# PCB_ESP_BUCK_PS.net
KiCad netlist of a schematic drawn in EAGLE
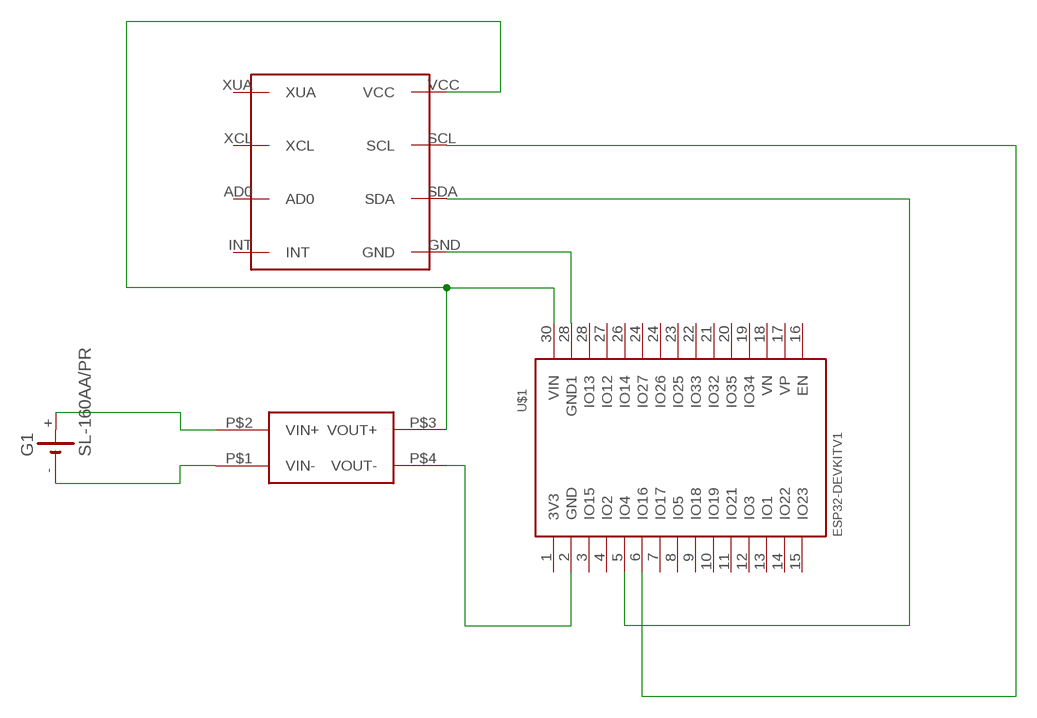
[diagram p0: schematic, sheet 1]

(export (version "E")
  (design (tool "Eeschema 10.0.6"))
  (components
    (comp (ref "G1")
      (value "SL-160AA/PR")
      (footprint "eagle-import:SL-160AA_PR")
      (libsource (lib "eagle-import") (part "SL-160AA/PR"))
    )
    (comp (ref "U$1")
      (value "ESP32DEVKITV1")
      (footprint "eagle-import:ESP32-DEVKITV1")
      (libsource (lib "eagle-import") (part "ESP32DEVKITV1"))
    )
    (comp (ref "U$2")
      (value "MP1584-MINI")
      (footprint "eagle-import:MINI-DC-BRICK")
      (libsource (lib "eagle-import") (part "MP1584-MINI"))
    )
    (comp (ref "U$3")
      (value "MPU-6050")
      (footprint "eagle-import:MPU-6050")
      (libsource (lib "eagle-import") (part "MPU-6050"))
    )
  )
  (nets
    (net (code "1") (name "Net-(U$1-GND)") (class "Default")
      (node (ref "U$1") (pin "2") (pinfunction "GND_2") (pintype "bidirectional"))
      (node (ref "U$2") (pin "P$4") (pinfunction "VOUT-_P$4") (pintype "output"))
    )
    (net (code "2") (name "Net-(U$1-GND1)") (class "Default")
      (node (ref "U$1") (pin "28") (pinfunction "GND1_28") (pintype "bidirectional"))
      (node (ref "U$3") (pin "GND") (pinfunction "GND_GND") (pintype "bidirectional"))
    )
    (net (code "3") (name "Net-(U$1-IO4)") (class "Default")
      (node (ref "U$1") (pin "5") (pinfunction "IO4_5") (pintype "bidirectional"))
      (node (ref "U$3") (pin "SDA") (pinfunction "SDA_SDA") (pintype "bidirectional"))
    )
    (net (code "4") (name "Net-(U$1-IO16)") (class "Default")
      (node (ref "U$1") (pin "6") (pinfunction "IO16_6") (pintype "bidirectional"))
      (node (ref "U$3") (pin "SCL") (pinfunction "SCL_SCL") (pintype "bidirectional"))
    )
    (net (code "5") (name "Net-(U$1-VIN)") (class "Default")
      (node (ref "U$1") (pin "30") (pinfunction "VIN_30") (pintype "bidirectional"))
      (node (ref "U$2") (pin "P$3") (pinfunction "VOUT+_P$3") (pintype "output"))
      (node (ref "U$3") (pin "VCC") (pinfunction "VCC_VCC") (pintype "bidirectional"))
    )
    (net (code "6") (name "Net-(U$2-VIN+)") (class "Default")
      (node (ref "G1") (pin "+") (pinfunction "+_+") (pintype "passive"))
      (node (ref "U$2") (pin "P$2") (pinfunction "VIN+_P$2") (pintype "input"))
    )
    (net (code "7") (name "Net-(U$2-VIN-)") (class "Default")
      (node (ref "G1") (pin "-") (pinfunction "-_-") (pintype "passive"))
      (node (ref "U$2") (pin "P$1") (pinfunction "VIN-_P$1") (pintype "input"))
    )
    (net (code "8") (name "unconnected-(U$1-3V3-Pad1)") (class "Default")
      (node (ref "U$1") (pin "1") (pinfunction "3V3_1") (pintype "bidirectional"))
    )
    (net (code "9") (name "unconnected-(U$1-EN-Pad16)") (class "Default")
      (node (ref "U$1") (pin "16") (pinfunction "EN_16") (pintype "bidirectional"))
    )
    (net (code "10") (name "unconnected-(U$1-IO1-Pad13)") (class "Default")
      (node (ref "U$1") (pin "13") (pinfunction "IO1_13") (pintype "bidirectional"))
    )
    (net (code "11") (name "unconnected-(U$1-IO2-Pad4)") (class "Default")
      (node (ref "U$1") (pin "4") (pinfunction "IO2_4") (pintype "bidirectional"))
    )
    (net (code "12") (name "unconnected-(U$1-IO3-Pad12)") (class "Default")
      (node (ref "U$1") (pin "12") (pinfunction "IO3_12") (pintype "bidirectional"))
    )
    (net (code "13") (name "unconnected-(U$1-IO5-Pad8)") (class "Default")
      (node (ref "U$1") (pin "8") (pinfunction "IO5_8") (pintype "bidirectional"))
    )
    (net (code "14") (name "unconnected-(U$1-IO12-Pad27)") (class "Default")
      (node (ref "U$1") (pin "27") (pinfunction "IO12_27") (pintype "bidirectional"))
    )
    (net (code "15") (name "unconnected-(U$1-IO13-Pad28)") (class "Default")
      (node (ref "U$1") (pin "28") (pinfunction "IO13_28") (pintype "bidirectional"))
    )
    (net (code "16") (name "unconnected-(U$1-IO14-Pad26)") (class "Default")
      (node (ref "U$1") (pin "26") (pinfunction "IO14_26") (pintype "bidirectional"))
    )
    (net (code "17") (name "unconnected-(U$1-IO15-Pad3)") (class "Default")
      (node (ref "U$1") (pin "3") (pinfunction "IO15_3") (pintype "bidirectional"))
    )
    (net (code "18") (name "unconnected-(U$1-IO17-Pad7)") (class "Default")
      (node (ref "U$1") (pin "7") (pinfunction "IO17_7") (pintype "bidirectional"))
    )
    (net (code "19") (name "unconnected-(U$1-IO18-Pad9)") (class "Default")
      (node (ref "U$1") (pin "9") (pinfunction "IO18_9") (pintype "bidirectional"))
    )
    (net (code "20") (name "unconnected-(U$1-IO19-Pad10)") (class "Default")
      (node (ref "U$1") (pin "10") (pinfunction "IO19_10") (pintype "bidirectional"))
    )
    (net (code "21") (name "unconnected-(U$1-IO21-Pad11)") (class "Default")
      (node (ref "U$1") (pin "11") (pinfunction "IO21_11") (pintype "bidirectional"))
    )
    (net (code "22") (name "unconnected-(U$1-IO22-Pad14)") (class "Default")
      (node (ref "U$1") (pin "14") (pinfunction "IO22_14") (pintype "bidirectional"))
    )
    (net (code "23") (name "unconnected-(U$1-IO23-Pad15)") (class "Default")
      (node (ref "U$1") (pin "15") (pinfunction "IO23_15") (pintype "bidirectional"))
    )
    (net (code "24") (name "unconnected-(U$1-IO25-Pad23)") (class "Default")
      (node (ref "U$1") (pin "23") (pinfunction "IO25_23") (pintype "bidirectional"))
    )
    (net (code "25") (name "unconnected-(U$1-IO26-Pad24)") (class "Default")
      (node (ref "U$1") (pin "24") (pinfunction "IO26_24") (pintype "bidirectional"))
    )
    (net (code "26") (name "unconnected-(U$1-IO27-Pad24)") (class "Default")
      (node (ref "U$1") (pin "24") (pinfunction "IO27_24") (pintype "bidirectional"))
    )
    (net (code "27") (name "unconnected-(U$1-IO32-Pad21)") (class "Default")
      (node (ref "U$1") (pin "21") (pinfunction "IO32_21") (pintype "bidirectional"))
    )
    (net (code "28") (name "unconnected-(U$1-IO33-Pad22)") (class "Default")
      (node (ref "U$1") (pin "22") (pinfunction "IO33_22") (pintype "bidirectional"))
    )
    (net (code "29") (name "unconnected-(U$1-IO34-Pad19)") (class "Default")
      (node (ref "U$1") (pin "19") (pinfunction "IO34_19") (pintype "bidirectional"))
    )
    (net (code "30") (name "unconnected-(U$1-IO35-Pad20)") (class "Default")
      (node (ref "U$1") (pin "20") (pinfunction "IO35_20") (pintype "bidirectional"))
    )
    (net (code "31") (name "unconnected-(U$1-VN-Pad18)") (class "Default")
      (node (ref "U$1") (pin "18") (pinfunction "VN_18") (pintype "bidirectional"))
    )
    (net (code "32") (name "unconnected-(U$1-VP-Pad17)") (class "Default")
      (node (ref "U$1") (pin "17") (pinfunction "VP_17") (pintype "bidirectional"))
    )
    (net (code "33") (name "unconnected-(U$3-PadAD0)") (class "Default")
      (node (ref "U$3") (pin "AD0") (pinfunction "AD0_AD0") (pintype "bidirectional"))
    )
    (net (code "34") (name "unconnected-(U$3-PadINT)") (class "Default")
      (node (ref "U$3") (pin "INT") (pinfunction "INT_INT") (pintype "bidirectional"))
    )
    (net (code "35") (name "unconnected-(U$3-PadXCL)") (class "Default")
      (node (ref "U$3") (pin "XCL") (pinfunction "XCL_XCL") (pintype "bidirectional"))
    )
    (net (code "36") (name "unconnected-(U$3-PadXUA)") (class "Default")
      (node (ref "U$3") (pin "XUA") (pinfunction "XUA_XUA") (pintype "bidirectional"))
    )
  )
)
